# axoloti_micro_modular_001.net
KiCad netlist of a schematic drawn in EAGLE
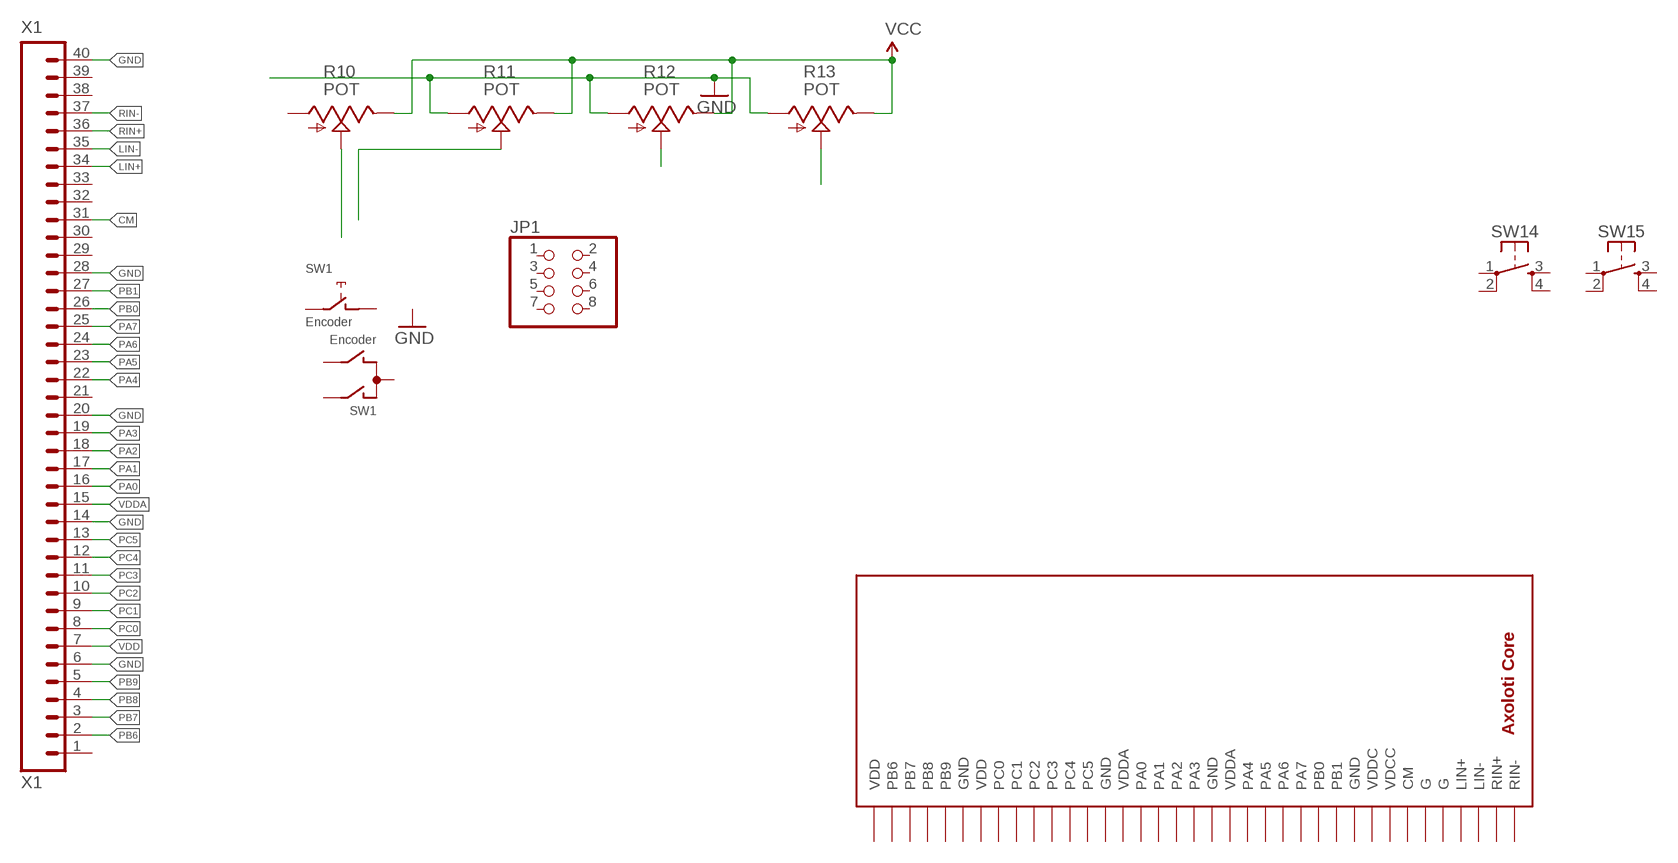
[diagram p0: schematic, sheet 1]

(export (version "E")
  (design (tool "Eeschema 10.0.6"))
  (components
    (comp (ref "JP1")
      (value "PINHD-2X4")
      (footprint "eagle-import:2X04")
      (libsource (lib "eagle-import") (part "PINHD-2X4"))
    )
    (comp (ref "R10")
      (value "POT")
      (footprint "eagle-import:ALPS_POT_SFE")
      (libsource (lib "eagle-import") (part "POT_US"))
    )
    (comp (ref "R11")
      (value "POT")
      (footprint "eagle-import:ALPS_POT_SFE")
      (libsource (lib "eagle-import") (part "POT_US"))
    )
    (comp (ref "R12")
      (value "POT")
      (footprint "eagle-import:ALPS_POT_SFE")
      (libsource (lib "eagle-import") (part "POT_US"))
    )
    (comp (ref "R13")
      (value "POT")
      (footprint "eagle-import:ALPS_POT_SFE")
      (libsource (lib "eagle-import") (part "POT_US"))
    )
    (comp (ref "SW1")
      (value "Encoder")
      (footprint "eagle-import:ALPS_EC12E_SW")
      (libsource (lib "eagle-import") (part "EC12E_SW"))
    )
    (comp (ref "SW14")
      (value "SW-TACTILE-6X6")
      (footprint "eagle-import:SW6X6")
      (libsource (lib "eagle-import") (part "SW-TACTILE-6X6"))
    )
    (comp (ref "SW15")
      (value "SW-TACTILE-6X6")
      (footprint "eagle-import:SW6X6")
      (libsource (lib "eagle-import") (part "SW-TACTILE-6X6"))
    )
    (comp (ref "U$1")
      (value "AXOLOTI_SHIELD_CUTOUT")
      (footprint "eagle-import:AXOLOTI_SHIELD_CUTOUT")
      (libsource (lib "eagle-import") (part "AXOLOTI_SHIELD_CUTOUT"))
    )
    (comp (ref "X1")
      (value "X1")
      (footprint "eagle-import:1X40")
      (libsource (lib "eagle-import") (part "M40"))
    )
  )
  (nets
    (net (code "1") (name "CM") (class "Default")
      (node (ref "X1") (pin "31") (pinfunction "31_31") (pintype "passive"))
    )
    (net (code "2") (name "GND") (class "Default")
      (node (ref "R11") (pin "P$3") (pinfunction "A_P$3") (pintype "passive"))
      (node (ref "R12") (pin "P$3") (pinfunction "A_P$3") (pintype "passive"))
      (node (ref "R13") (pin "P$3") (pinfunction "A_P$3") (pintype "passive"))
      (node (ref "X1") (pin "14") (pinfunction "14_14") (pintype "passive"))
      (node (ref "X1") (pin "20") (pinfunction "20_20") (pintype "passive"))
      (node (ref "X1") (pin "28") (pinfunction "28_28") (pintype "passive"))
      (node (ref "X1") (pin "40") (pinfunction "40_40") (pintype "passive"))
      (node (ref "X1") (pin "6") (pinfunction "6_6") (pintype "passive"))
    )
    (net (code "3") (name "LIN+") (class "Default")
      (node (ref "X1") (pin "34") (pinfunction "34_34") (pintype "passive"))
    )
    (net (code "4") (name "LIN-") (class "Default")
      (node (ref "X1") (pin "35") (pinfunction "35_35") (pintype "passive"))
    )
    (net (code "5") (name "PA0") (class "Default")
      (node (ref "X1") (pin "16") (pinfunction "16_16") (pintype "passive"))
    )
    (net (code "6") (name "PA1") (class "Default")
      (node (ref "X1") (pin "17") (pinfunction "17_17") (pintype "passive"))
    )
    (net (code "7") (name "PA2") (class "Default")
      (node (ref "X1") (pin "18") (pinfunction "18_18") (pintype "passive"))
    )
    (net (code "8") (name "PA3") (class "Default")
      (node (ref "X1") (pin "19") (pinfunction "19_19") (pintype "passive"))
    )
    (net (code "9") (name "PA4") (class "Default")
      (node (ref "X1") (pin "22") (pinfunction "22_22") (pintype "passive"))
    )
    (net (code "10") (name "PA5") (class "Default")
      (node (ref "X1") (pin "23") (pinfunction "23_23") (pintype "passive"))
    )
    (net (code "11") (name "PA6") (class "Default")
      (node (ref "X1") (pin "24") (pinfunction "24_24") (pintype "passive"))
    )
    (net (code "12") (name "PA7") (class "Default")
      (node (ref "X1") (pin "25") (pinfunction "25_25") (pintype "passive"))
    )
    (net (code "13") (name "PB0") (class "Default")
      (node (ref "X1") (pin "26") (pinfunction "26_26") (pintype "passive"))
    )
    (net (code "14") (name "PB1") (class "Default")
      (node (ref "X1") (pin "27") (pinfunction "27_27") (pintype "passive"))
    )
    (net (code "15") (name "PB6") (class "Default")
      (node (ref "X1") (pin "2") (pinfunction "2_2") (pintype "passive"))
    )
    (net (code "16") (name "PB7") (class "Default")
      (node (ref "X1") (pin "3") (pinfunction "3_3") (pintype "passive"))
    )
    (net (code "17") (name "PB8") (class "Default")
      (node (ref "X1") (pin "4") (pinfunction "4_4") (pintype "passive"))
    )
    (net (code "18") (name "PB9") (class "Default")
      (node (ref "X1") (pin "5") (pinfunction "5_5") (pintype "passive"))
    )
    (net (code "19") (name "PC0") (class "Default")
      (node (ref "X1") (pin "8") (pinfunction "8_8") (pintype "passive"))
    )
    (net (code "20") (name "PC1") (class "Default")
      (node (ref "X1") (pin "9") (pinfunction "9_9") (pintype "passive"))
    )
    (net (code "21") (name "PC2") (class "Default")
      (node (ref "X1") (pin "10") (pinfunction "10_10") (pintype "passive"))
    )
    (net (code "22") (name "PC3") (class "Default")
      (node (ref "X1") (pin "11") (pinfunction "11_11") (pintype "passive"))
    )
    (net (code "23") (name "PC4") (class "Default")
      (node (ref "X1") (pin "12") (pinfunction "12_12") (pintype "passive"))
    )
    (net (code "24") (name "PC5") (class "Default")
      (node (ref "X1") (pin "13") (pinfunction "13_13") (pintype "passive"))
    )
    (net (code "25") (name "RIN+") (class "Default")
      (node (ref "X1") (pin "36") (pinfunction "36_36") (pintype "passive"))
    )
    (net (code "26") (name "RIN-") (class "Default")
      (node (ref "X1") (pin "37") (pinfunction "37_37") (pintype "passive"))
    )
    (net (code "27") (name "VCC") (class "Default")
      (node (ref "R10") (pin "P$1") (pinfunction "E_P$1") (pintype "passive"))
      (node (ref "R11") (pin "P$1") (pinfunction "E_P$1") (pintype "passive"))
      (node (ref "R12") (pin "P$1") (pinfunction "E_P$1") (pintype "passive"))
      (node (ref "R13") (pin "P$1") (pinfunction "E_P$1") (pintype "passive"))
    )
    (net (code "28") (name "VDD") (class "Default")
      (node (ref "X1") (pin "7") (pinfunction "7_7") (pintype "passive"))
    )
    (net (code "29") (name "VDDA") (class "Default")
      (node (ref "X1") (pin "15") (pinfunction "15_15") (pintype "passive"))
    )
    (net (code "30") (name "unconnected-(JP1-Pad1)") (class "Default")
      (node (ref "JP1") (pin "1") (pinfunction "1_1") (pintype "passive"))
    )
    (net (code "31") (name "unconnected-(JP1-Pad2)") (class "Default")
      (node (ref "JP1") (pin "2") (pinfunction "2_2") (pintype "passive"))
    )
    (net (code "32") (name "unconnected-(JP1-Pad3)") (class "Default")
      (node (ref "JP1") (pin "3") (pinfunction "3_3") (pintype "passive"))
    )
    (net (code "33") (name "unconnected-(JP1-Pad4)") (class "Default")
      (node (ref "JP1") (pin "4") (pinfunction "4_4") (pintype "passive"))
    )
    (net (code "34") (name "unconnected-(JP1-Pad5)") (class "Default")
      (node (ref "JP1") (pin "5") (pinfunction "5_5") (pintype "passive"))
    )
    (net (code "35") (name "unconnected-(JP1-Pad6)") (class "Default")
      (node (ref "JP1") (pin "6") (pinfunction "6_6") (pintype "passive"))
    )
    (net (code "36") (name "unconnected-(JP1-Pad7)") (class "Default")
      (node (ref "JP1") (pin "7") (pinfunction "7_7") (pintype "passive"))
    )
    (net (code "37") (name "unconnected-(JP1-Pad8)") (class "Default")
      (node (ref "JP1") (pin "8") (pinfunction "8_8") (pintype "passive"))
    )
    (net (code "38") (name "unconnected-(R10-A-PadP$3)") (class "Default")
      (node (ref "R10") (pin "P$3") (pinfunction "A_P$3") (pintype "passive"))
    )
    (net (code "39") (name "unconnected-(R10-S-PadP$2)") (class "Default")
      (node (ref "R10") (pin "P$2") (pinfunction "S_P$2") (pintype "passive"))
    )
    (net (code "40") (name "unconnected-(R11-S-PadP$2)") (class "Default")
      (node (ref "R11") (pin "P$2") (pinfunction "S_P$2") (pintype "passive"))
    )
    (net (code "41") (name "unconnected-(R12-S-PadP$2)") (class "Default")
      (node (ref "R12") (pin "P$2") (pinfunction "S_P$2") (pintype "passive"))
    )
    (net (code "42") (name "unconnected-(R13-S-PadP$2)") (class "Default")
      (node (ref "R13") (pin "P$2") (pinfunction "S_P$2") (pintype "passive"))
    )
    (net (code "43") (name "unconnected-(SW1-PadA)") (class "Default")
      (node (ref "SW1") (pin "A") (pinfunction "A_A") (pintype "passive"))
    )
    (net (code "44") (name "unconnected-(SW1-PadB)") (class "Default")
      (node (ref "SW1") (pin "B") (pinfunction "B_B") (pintype "passive"))
    )
    (net (code "45") (name "unconnected-(SW1-PadC)") (class "Default")
      (node (ref "SW1") (pin "C") (pinfunction "C_C") (pintype "passive"))
    )
    (net (code "46") (name "unconnected-(SW1B-1-PadD)") (class "Default")
      (node (ref "SW1") (pin "D") (pinfunction "1_D") (pintype "passive"))
    )
    (net (code "47") (name "unconnected-(SW1B-2-PadE)") (class "Default")
      (node (ref "SW1") (pin "E") (pinfunction "2_E") (pintype "passive"))
    )
    (net (code "48") (name "unconnected-(SW14-P1-Pad1)") (class "Default")
      (node (ref "SW14") (pin "1") (pinfunction "P1_1") (pintype "passive"))
    )
    (net (code "49") (name "unconnected-(SW14-P2-Pad2)") (class "Default")
      (node (ref "SW14") (pin "2") (pinfunction "P2_2") (pintype "passive"))
    )
    (net (code "50") (name "unconnected-(SW14-S1-Pad3)") (class "Default")
      (node (ref "SW14") (pin "3") (pinfunction "S1_3") (pintype "passive"))
    )
    (net (code "51") (name "unconnected-(SW14-S2-Pad4)") (class "Default")
      (node (ref "SW14") (pin "4") (pinfunction "S2_4") (pintype "passive"))
    )
    (net (code "52") (name "unconnected-(SW15-P1-Pad1)") (class "Default")
      (node (ref "SW15") (pin "1") (pinfunction "P1_1") (pintype "passive"))
    )
    (net (code "53") (name "unconnected-(SW15-P2-Pad2)") (class "Default")
      (node (ref "SW15") (pin "2") (pinfunction "P2_2") (pintype "passive"))
    )
    (net (code "54") (name "unconnected-(SW15-S1-Pad3)") (class "Default")
      (node (ref "SW15") (pin "3") (pinfunction "S1_3") (pintype "passive"))
    )
    (net (code "55") (name "unconnected-(SW15-S2-Pad4)") (class "Default")
      (node (ref "SW15") (pin "4") (pinfunction "S2_4") (pintype "passive"))
    )
    (net (code "56") (name "unconnected-(U$1-G-PadG1)") (class "Default")
      (node (ref "U$1") (pin "G1") (pinfunction "G_G1") (pintype "bidirectional"))
    )
    (net (code "57") (name "unconnected-(U$1-G-PadG2)") (class "Default")
      (node (ref "U$1") (pin "G2") (pinfunction "G_G2") (pintype "bidirectional"))
    )
    (net (code "58") (name "unconnected-(U$1-GND-PadGND1)") (class "Default")
      (node (ref "U$1") (pin "GND1") (pinfunction "GND_GND1") (pintype "bidirectional"))
    )
    (net (code "59") (name "unconnected-(U$1-GND-PadGND2)") (class "Default")
      (node (ref "U$1") (pin "GND2") (pinfunction "GND_GND2") (pintype "bidirectional"))
    )
    (net (code "60") (name "unconnected-(U$1-GND-PadGND3)") (class "Default")
      (node (ref "U$1") (pin "GND3") (pinfunction "GND_GND3") (pintype "bidirectional"))
    )
    (net (code "61") (name "unconnected-(U$1-GND-PadGND4)") (class "Default")
      (node (ref "U$1") (pin "GND4") (pinfunction "GND_GND4") (pintype "bidirectional"))
    )
    (net (code "62") (name "unconnected-(U$1-PadCM)") (class "Default")
      (node (ref "U$1") (pin "CM") (pinfunction "CM_CM") (pintype "bidirectional"))
    )
    (net (code "63") (name "unconnected-(U$1-PadLIN+)") (class "Default")
      (node (ref "U$1") (pin "LIN+") (pinfunction "LIN+_LIN+") (pintype "bidirectional"))
    )
    (net (code "64") (name "unconnected-(U$1-PadLIN-)") (class "Default")
      (node (ref "U$1") (pin "LIN-") (pinfunction "LIN-_LIN-") (pintype "bidirectional"))
    )
    (net (code "65") (name "unconnected-(U$1-PadPA0)") (class "Default")
      (node (ref "U$1") (pin "PA0") (pinfunction "PA0_PA0") (pintype "bidirectional"))
    )
    (net (code "66") (name "unconnected-(U$1-PadPA1)") (class "Default")
      (node (ref "U$1") (pin "PA1") (pinfunction "PA1_PA1") (pintype "bidirectional"))
    )
    (net (code "67") (name "unconnected-(U$1-PadPA2)") (class "Default")
      (node (ref "U$1") (pin "PA2") (pinfunction "PA2_PA2") (pintype "bidirectional"))
    )
    (net (code "68") (name "unconnected-(U$1-PadPA3)") (class "Default")
      (node (ref "U$1") (pin "PA3") (pinfunction "PA3_PA3") (pintype "bidirectional"))
    )
    (net (code "69") (name "unconnected-(U$1-PadPA4)") (class "Default")
      (node (ref "U$1") (pin "PA4") (pinfunction "PA4_PA4") (pintype "bidirectional"))
    )
    (net (code "70") (name "unconnected-(U$1-PadPA5)") (class "Default")
      (node (ref "U$1") (pin "PA5") (pinfunction "PA5_PA5") (pintype "bidirectional"))
    )
    (net (code "71") (name "unconnected-(U$1-PadPA6)") (class "Default")
      (node (ref "U$1") (pin "PA6") (pinfunction "PA6_PA6") (pintype "bidirectional"))
    )
    (net (code "72") (name "unconnected-(U$1-PadPA7)") (class "Default")
      (node (ref "U$1") (pin "PA7") (pinfunction "PA7_PA7") (pintype "bidirectional"))
    )
    (net (code "73") (name "unconnected-(U$1-PadPB0)") (class "Default")
      (node (ref "U$1") (pin "PB0") (pinfunction "PB0_PB0") (pintype "bidirectional"))
    )
    (net (code "74") (name "unconnected-(U$1-PadPB1)") (class "Default")
      (node (ref "U$1") (pin "PB1") (pinfunction "PB1_PB1") (pintype "bidirectional"))
    )
    (net (code "75") (name "unconnected-(U$1-PadPB6)") (class "Default")
      (node (ref "U$1") (pin "PB6") (pinfunction "PB6_PB6") (pintype "bidirectional"))
    )
    (net (code "76") (name "unconnected-(U$1-PadPB7)") (class "Default")
      (node (ref "U$1") (pin "PB7") (pinfunction "PB7_PB7") (pintype "bidirectional"))
    )
    (net (code "77") (name "unconnected-(U$1-PadPB8)") (class "Default")
      (node (ref "U$1") (pin "PB8") (pinfunction "PB8_PB8") (pintype "bidirectional"))
    )
    (net (code "78") (name "unconnected-(U$1-PadPB9)") (class "Default")
      (node (ref "U$1") (pin "PB9") (pinfunction "PB9_PB9") (pintype "bidirectional"))
    )
    (net (code "79") (name "unconnected-(U$1-PadPC0)") (class "Default")
      (node (ref "U$1") (pin "PC0") (pinfunction "PC0_PC0") (pintype "bidirectional"))
    )
    (net (code "80") (name "unconnected-(U$1-PadPC1)") (class "Default")
      (node (ref "U$1") (pin "PC1") (pinfunction "PC1_PC1") (pintype "bidirectional"))
    )
    (net (code "81") (name "unconnected-(U$1-PadPC2)") (class "Default")
      (node (ref "U$1") (pin "PC2") (pinfunction "PC2_PC2") (pintype "bidirectional"))
    )
    (net (code "82") (name "unconnected-(U$1-PadPC3)") (class "Default")
      (node (ref "U$1") (pin "PC3") (pinfunction "PC3_PC3") (pintype "bidirectional"))
    )
    (net (code "83") (name "unconnected-(U$1-PadPC4)") (class "Default")
      (node (ref "U$1") (pin "PC4") (pinfunction "PC4_PC4") (pintype "bidirectional"))
    )
    (net (code "84") (name "unconnected-(U$1-PadPC5)") (class "Default")
      (node (ref "U$1") (pin "PC5") (pinfunction "PC5_PC5") (pintype "bidirectional"))
    )
    (net (code "85") (name "unconnected-(U$1-PadRIN+)") (class "Default")
      (node (ref "U$1") (pin "RIN+") (pinfunction "RIN+_RIN+") (pintype "bidirectional"))
    )
    (net (code "86") (name "unconnected-(U$1-PadRIN-)") (class "Default")
      (node (ref "U$1") (pin "RIN-") (pinfunction "RIN-_RIN-") (pintype "bidirectional"))
    )
    (net (code "87") (name "unconnected-(U$1-VDCC-PadVDDC2)") (class "Default")
      (node (ref "U$1") (pin "VDDC2") (pinfunction "VDCC_VDDC2") (pintype "bidirectional"))
    )
    (net (code "88") (name "unconnected-(U$1-VDD-PadVDD@1)") (class "Default")
      (node (ref "U$1") (pin "VDD@1") (pinfunction "VDD_VDD@1") (pintype "bidirectional"))
    )
    (net (code "89") (name "unconnected-(U$1-VDD-PadVDD@2)") (class "Default")
      (node (ref "U$1") (pin "VDD@2") (pinfunction "VDD_VDD@2") (pintype "bidirectional"))
    )
    (net (code "90") (name "unconnected-(U$1-VDDA-PadVDDA1)") (class "Default")
      (node (ref "U$1") (pin "VDDA1") (pinfunction "VDDA_VDDA1") (pintype "bidirectional"))
    )
    (net (code "91") (name "unconnected-(U$1-VDDA-PadVDDA2)") (class "Default")
      (node (ref "U$1") (pin "VDDA2") (pinfunction "VDDA_VDDA2") (pintype "bidirectional"))
    )
    (net (code "92") (name "unconnected-(U$1-VDDC-PadVDDC1)") (class "Default")
      (node (ref "U$1") (pin "VDDC1") (pinfunction "VDDC_VDDC1") (pintype "bidirectional"))
    )
    (net (code "93") (name "unconnected-(X1-Pad1)") (class "Default")
      (node (ref "X1") (pin "1") (pinfunction "1_1") (pintype "passive"))
    )
    (net (code "94") (name "unconnected-(X1-Pad21)") (class "Default")
      (node (ref "X1") (pin "21") (pinfunction "21_21") (pintype "passive"))
    )
    (net (code "95") (name "unconnected-(X1-Pad29)") (class "Default")
      (node (ref "X1") (pin "29") (pinfunction "29_29") (pintype "passive"))
    )
    (net (code "96") (name "unconnected-(X1-Pad30)") (class "Default")
      (node (ref "X1") (pin "30") (pinfunction "30_30") (pintype "passive"))
    )
    (net (code "97") (name "unconnected-(X1-Pad32)") (class "Default")
      (node (ref "X1") (pin "32") (pinfunction "32_32") (pintype "passive"))
    )
    (net (code "98") (name "unconnected-(X1-Pad33)") (class "Default")
      (node (ref "X1") (pin "33") (pinfunction "33_33") (pintype "passive"))
    )
    (net (code "99") (name "unconnected-(X1-Pad38)") (class "Default")
      (node (ref "X1") (pin "38") (pinfunction "38_38") (pintype "passive"))
    )
    (net (code "100") (name "unconnected-(X1-Pad39)") (class "Default")
      (node (ref "X1") (pin "39") (pinfunction "39_39") (pintype "passive"))
    )
  )
)
